# ALU.net
KiCad netlist of a schematic drawn in Altium Designer
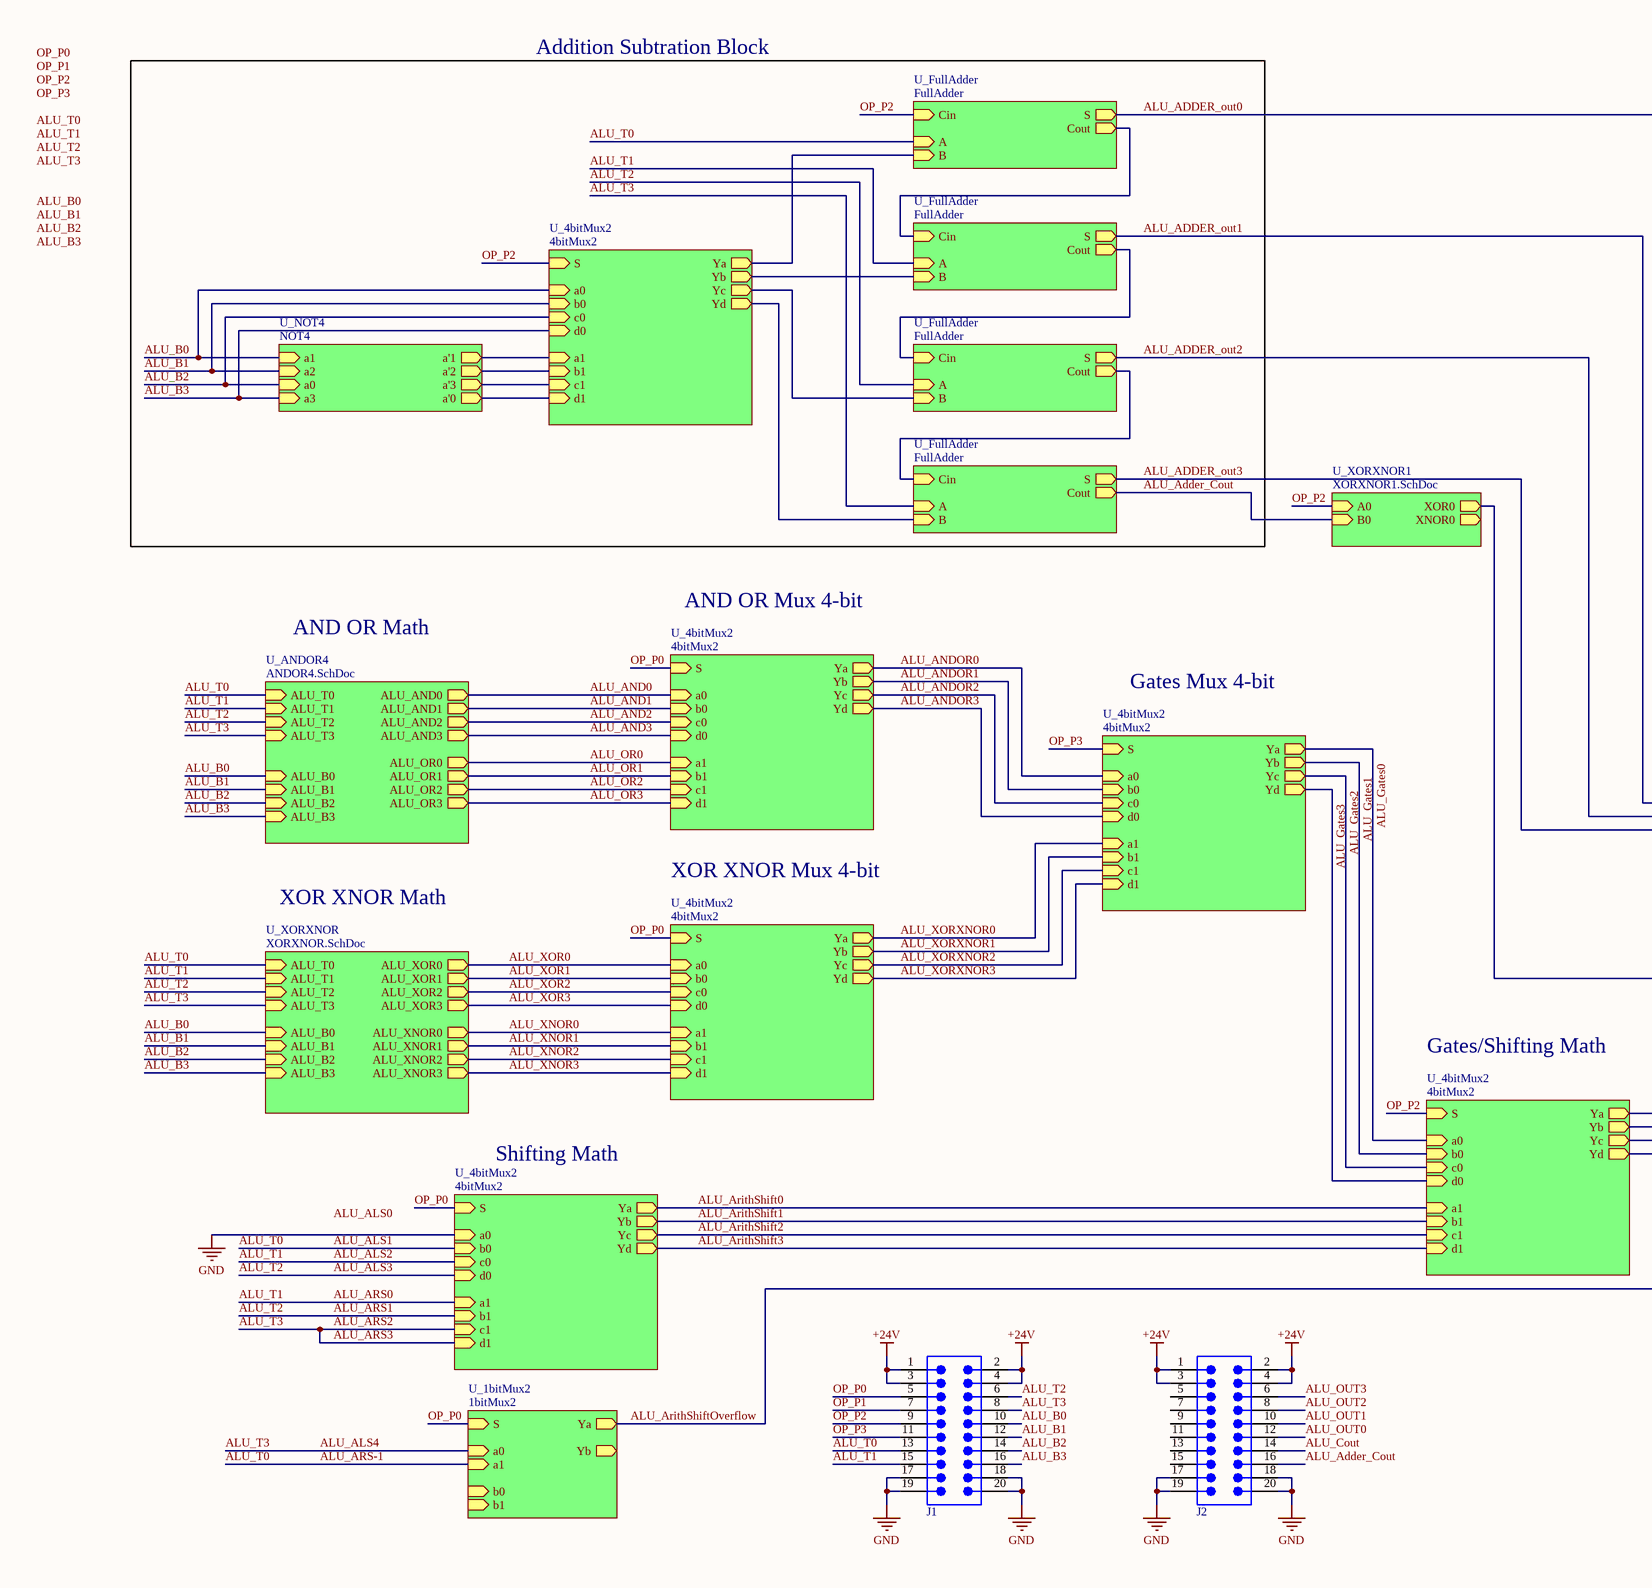
[diagram p0: ALU.SchDoc, left]
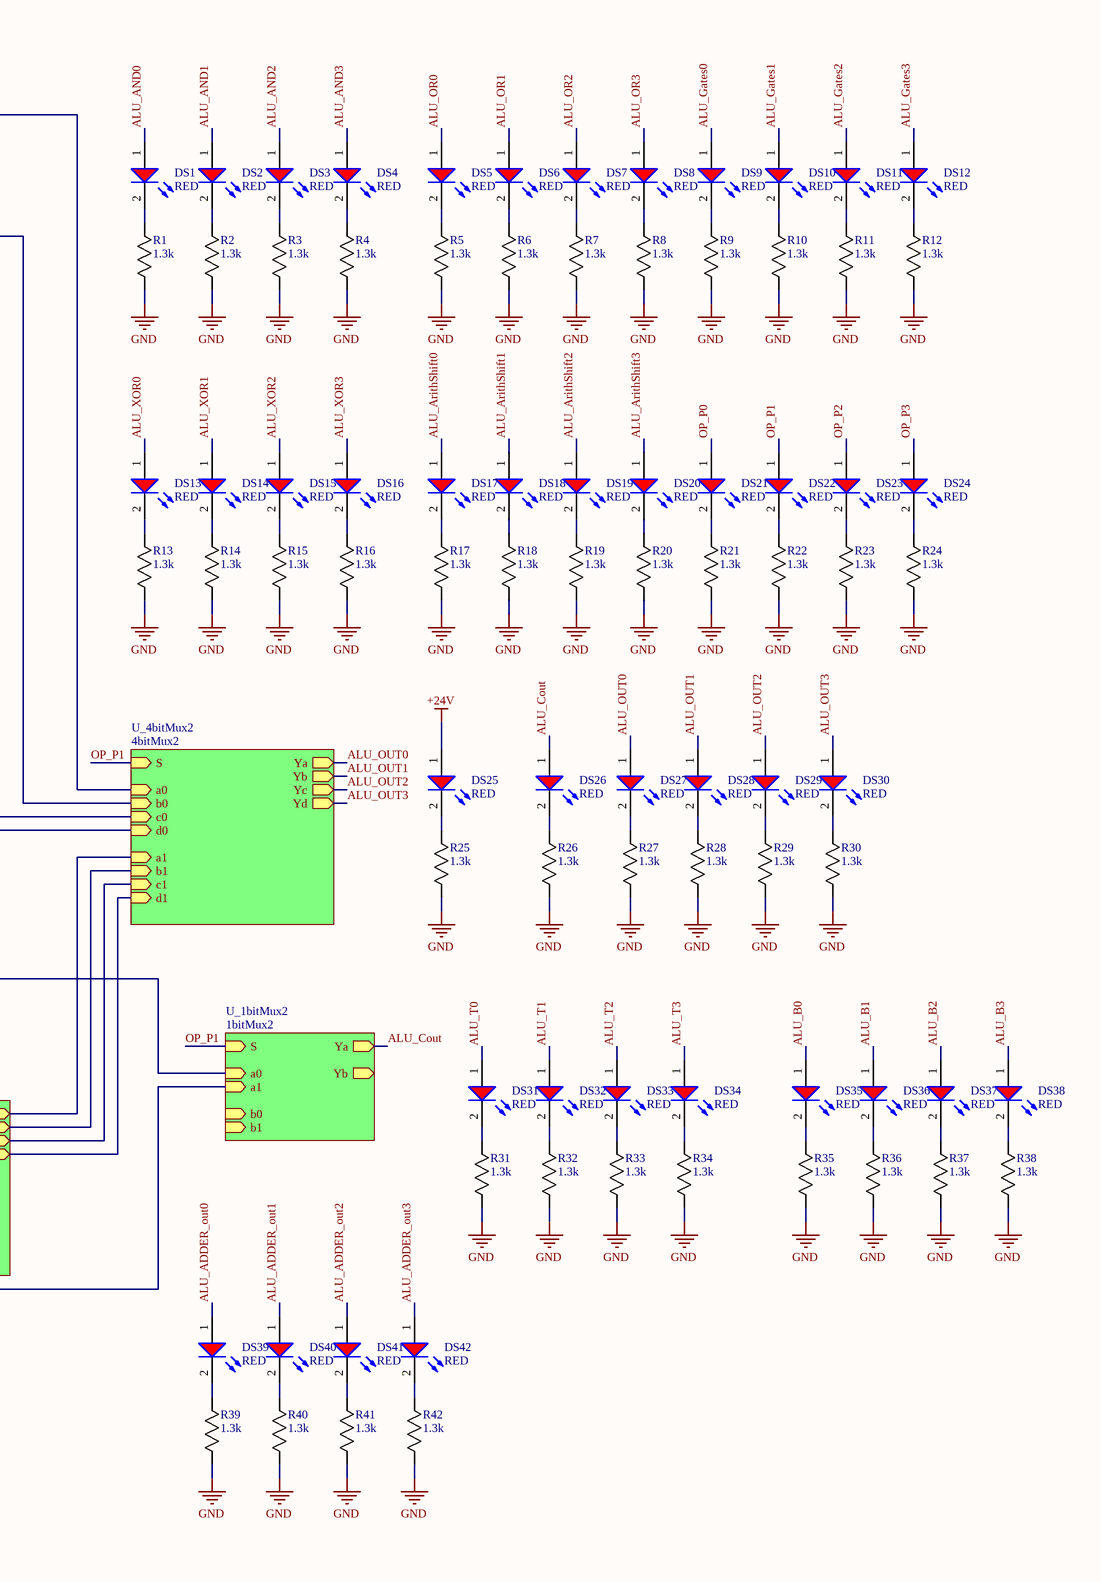
[diagram p1: ALU.SchDoc, right]

(export (version "E")
  (design (tool "Eeschema 10.0.6"))
  (components
    (comp (ref "DS1")
      (value "RED")
      (footprint "LED RED 151051RS11000")
      (description "WL-TMRC Red Color Diffused 5 mm Round Through Hole LED")
      (fields
        (field (name "MANUFACTURER") "Wurth Elektronik")
        (field (name "MANUFACTURER PART NUMBER") "151051RS11000")
      )
      (libsource (lib "Schlib1") (part "LED RED 151051RS11000"))
    )
    (comp (ref "DS2")
      (value "RED")
      (footprint "LED RED 151051RS11000")
      (description "WL-TMRC Red Color Diffused 5 mm Round Through Hole LED")
      (fields
        (field (name "MANUFACTURER") "Wurth Elektronik")
        (field (name "MANUFACTURER PART NUMBER") "151051RS11000")
      )
      (libsource (lib "Schlib1") (part "LED RED 151051RS11000"))
    )
    (comp (ref "DS3")
      (value "RED")
      (footprint "LED RED 151051RS11000")
      (description "WL-TMRC Red Color Diffused 5 mm Round Through Hole LED")
      (fields
        (field (name "MANUFACTURER") "Wurth Elektronik")
        (field (name "MANUFACTURER PART NUMBER") "151051RS11000")
      )
      (libsource (lib "Schlib1") (part "LED RED 151051RS11000"))
    )
    (comp (ref "DS4")
      (value "RED")
      (footprint "LED RED 151051RS11000")
      (description "WL-TMRC Red Color Diffused 5 mm Round Through Hole LED")
      (fields
        (field (name "MANUFACTURER") "Wurth Elektronik")
        (field (name "MANUFACTURER PART NUMBER") "151051RS11000")
      )
      (libsource (lib "Schlib1") (part "LED RED 151051RS11000"))
    )
    (comp (ref "DS5")
      (value "RED")
      (footprint "LED RED 151051RS11000")
      (description "WL-TMRC Red Color Diffused 5 mm Round Through Hole LED")
      (fields
        (field (name "MANUFACTURER") "Wurth Elektronik")
        (field (name "MANUFACTURER PART NUMBER") "151051RS11000")
      )
      (libsource (lib "Schlib1") (part "LED RED 151051RS11000"))
    )
    (comp (ref "DS6")
      (value "RED")
      (footprint "LED RED 151051RS11000")
      (description "WL-TMRC Red Color Diffused 5 mm Round Through Hole LED")
      (fields
        (field (name "MANUFACTURER") "Wurth Elektronik")
        (field (name "MANUFACTURER PART NUMBER") "151051RS11000")
      )
      (libsource (lib "Schlib1") (part "LED RED 151051RS11000"))
    )
    (comp (ref "DS7")
      (value "RED")
      (footprint "LED RED 151051RS11000")
      (description "WL-TMRC Red Color Diffused 5 mm Round Through Hole LED")
      (fields
        (field (name "MANUFACTURER") "Wurth Elektronik")
        (field (name "MANUFACTURER PART NUMBER") "151051RS11000")
      )
      (libsource (lib "Schlib1") (part "LED RED 151051RS11000"))
    )
    (comp (ref "DS8")
      (value "RED")
      (footprint "LED RED 151051RS11000")
      (description "WL-TMRC Red Color Diffused 5 mm Round Through Hole LED")
      (fields
        (field (name "MANUFACTURER") "Wurth Elektronik")
        (field (name "MANUFACTURER PART NUMBER") "151051RS11000")
      )
      (libsource (lib "Schlib1") (part "LED RED 151051RS11000"))
    )
    (comp (ref "DS9")
      (value "RED")
      (footprint "LED RED 151051RS11000")
      (description "WL-TMRC Red Color Diffused 5 mm Round Through Hole LED")
      (fields
        (field (name "MANUFACTURER") "Wurth Elektronik")
        (field (name "MANUFACTURER PART NUMBER") "151051RS11000")
      )
      (libsource (lib "Schlib1") (part "LED RED 151051RS11000"))
    )
    (comp (ref "DS10")
      (value "RED")
      (footprint "LED RED 151051RS11000")
      (description "WL-TMRC Red Color Diffused 5 mm Round Through Hole LED")
      (fields
        (field (name "MANUFACTURER") "Wurth Elektronik")
        (field (name "MANUFACTURER PART NUMBER") "151051RS11000")
      )
      (libsource (lib "Schlib1") (part "LED RED 151051RS11000"))
    )
    (comp (ref "DS11")
      (value "RED")
      (footprint "LED RED 151051RS11000")
      (description "WL-TMRC Red Color Diffused 5 mm Round Through Hole LED")
      (fields
        (field (name "MANUFACTURER") "Wurth Elektronik")
        (field (name "MANUFACTURER PART NUMBER") "151051RS11000")
      )
      (libsource (lib "Schlib1") (part "LED RED 151051RS11000"))
    )
    (comp (ref "DS12")
      (value "RED")
      (footprint "LED RED 151051RS11000")
      (description "WL-TMRC Red Color Diffused 5 mm Round Through Hole LED")
      (fields
        (field (name "MANUFACTURER") "Wurth Elektronik")
        (field (name "MANUFACTURER PART NUMBER") "151051RS11000")
      )
      (libsource (lib "Schlib1") (part "LED RED 151051RS11000"))
    )
    (comp (ref "DS13")
      (value "RED")
      (footprint "LED RED 151051RS11000")
      (description "WL-TMRC Red Color Diffused 5 mm Round Through Hole LED")
      (fields
        (field (name "MANUFACTURER") "Wurth Elektronik")
        (field (name "MANUFACTURER PART NUMBER") "151051RS11000")
      )
      (libsource (lib "Schlib1") (part "LED RED 151051RS11000"))
    )
    (comp (ref "DS14")
      (value "RED")
      (footprint "LED RED 151051RS11000")
      (description "WL-TMRC Red Color Diffused 5 mm Round Through Hole LED")
      (fields
        (field (name "MANUFACTURER") "Wurth Elektronik")
        (field (name "MANUFACTURER PART NUMBER") "151051RS11000")
      )
      (libsource (lib "Schlib1") (part "LED RED 151051RS11000"))
    )
    (comp (ref "DS15")
      (value "RED")
      (footprint "LED RED 151051RS11000")
      (description "WL-TMRC Red Color Diffused 5 mm Round Through Hole LED")
      (fields
        (field (name "MANUFACTURER") "Wurth Elektronik")
        (field (name "MANUFACTURER PART NUMBER") "151051RS11000")
      )
      (libsource (lib "Schlib1") (part "LED RED 151051RS11000"))
    )
    (comp (ref "DS16")
      (value "RED")
      (footprint "LED RED 151051RS11000")
      (description "WL-TMRC Red Color Diffused 5 mm Round Through Hole LED")
      (fields
        (field (name "MANUFACTURER") "Wurth Elektronik")
        (field (name "MANUFACTURER PART NUMBER") "151051RS11000")
      )
      (libsource (lib "Schlib1") (part "LED RED 151051RS11000"))
    )
    (comp (ref "DS17")
      (value "RED")
      (footprint "LED RED 151051RS11000")
      (description "WL-TMRC Red Color Diffused 5 mm Round Through Hole LED")
      (fields
        (field (name "MANUFACTURER") "Wurth Elektronik")
        (field (name "MANUFACTURER PART NUMBER") "151051RS11000")
      )
      (libsource (lib "Schlib1") (part "LED RED 151051RS11000"))
    )
    (comp (ref "DS18")
      (value "RED")
      (footprint "LED RED 151051RS11000")
      (description "WL-TMRC Red Color Diffused 5 mm Round Through Hole LED")
      (fields
        (field (name "MANUFACTURER") "Wurth Elektronik")
        (field (name "MANUFACTURER PART NUMBER") "151051RS11000")
      )
      (libsource (lib "Schlib1") (part "LED RED 151051RS11000"))
    )
    (comp (ref "DS19")
      (value "RED")
      (footprint "LED RED 151051RS11000")
      (description "WL-TMRC Red Color Diffused 5 mm Round Through Hole LED")
      (fields
        (field (name "MANUFACTURER") "Wurth Elektronik")
        (field (name "MANUFACTURER PART NUMBER") "151051RS11000")
      )
      (libsource (lib "Schlib1") (part "LED RED 151051RS11000"))
    )
    (comp (ref "DS20")
      (value "RED")
      (footprint "LED RED 151051RS11000")
      (description "WL-TMRC Red Color Diffused 5 mm Round Through Hole LED")
      (fields
        (field (name "MANUFACTURER") "Wurth Elektronik")
        (field (name "MANUFACTURER PART NUMBER") "151051RS11000")
      )
      (libsource (lib "Schlib1") (part "LED RED 151051RS11000"))
    )
    (comp (ref "DS21")
      (value "RED")
      (footprint "LED RED 151051RS11000")
      (description "WL-TMRC Red Color Diffused 5 mm Round Through Hole LED")
      (fields
        (field (name "MANUFACTURER") "Wurth Elektronik")
        (field (name "MANUFACTURER PART NUMBER") "151051RS11000")
      )
      (libsource (lib "Schlib1") (part "LED RED 151051RS11000"))
    )
    (comp (ref "DS22")
      (value "RED")
      (footprint "LED RED 151051RS11000")
      (description "WL-TMRC Red Color Diffused 5 mm Round Through Hole LED")
      (fields
        (field (name "MANUFACTURER") "Wurth Elektronik")
        (field (name "MANUFACTURER PART NUMBER") "151051RS11000")
      )
      (libsource (lib "Schlib1") (part "LED RED 151051RS11000"))
    )
    (comp (ref "DS23")
      (value "RED")
      (footprint "LED RED 151051RS11000")
      (description "WL-TMRC Red Color Diffused 5 mm Round Through Hole LED")
      (fields
        (field (name "MANUFACTURER") "Wurth Elektronik")
        (field (name "MANUFACTURER PART NUMBER") "151051RS11000")
      )
      (libsource (lib "Schlib1") (part "LED RED 151051RS11000"))
    )
    (comp (ref "DS24")
      (value "RED")
      (footprint "LED RED 151051RS11000")
      (description "WL-TMRC Red Color Diffused 5 mm Round Through Hole LED")
      (fields
        (field (name "MANUFACTURER") "Wurth Elektronik")
        (field (name "MANUFACTURER PART NUMBER") "151051RS11000")
      )
      (libsource (lib "Schlib1") (part "LED RED 151051RS11000"))
    )
    (comp (ref "DS25")
      (value "RED")
      (footprint "LED RED 151051RS11000")
      (description "WL-TMRC Red Color Diffused 5 mm Round Through Hole LED")
      (fields
        (field (name "MANUFACTURER") "Wurth Elektronik")
        (field (name "MANUFACTURER PART NUMBER") "151051RS11000")
      )
      (libsource (lib "Schlib1") (part "LED RED 151051RS11000"))
    )
    (comp (ref "DS26")
      (value "RED")
      (footprint "LED RED 151051RS11000")
      (description "WL-TMRC Red Color Diffused 5 mm Round Through Hole LED")
      (fields
        (field (name "MANUFACTURER") "Wurth Elektronik")
        (field (name "MANUFACTURER PART NUMBER") "151051RS11000")
      )
      (libsource (lib "Schlib1") (part "LED RED 151051RS11000"))
    )
    (comp (ref "DS27")
      (value "RED")
      (footprint "LED RED 151051RS11000")
      (description "WL-TMRC Red Color Diffused 5 mm Round Through Hole LED")
      (fields
        (field (name "MANUFACTURER") "Wurth Elektronik")
        (field (name "MANUFACTURER PART NUMBER") "151051RS11000")
      )
      (libsource (lib "Schlib1") (part "LED RED 151051RS11000"))
    )
    (comp (ref "DS28")
      (value "RED")
      (footprint "LED RED 151051RS11000")
      (description "WL-TMRC Red Color Diffused 5 mm Round Through Hole LED")
      (fields
        (field (name "MANUFACTURER") "Wurth Elektronik")
        (field (name "MANUFACTURER PART NUMBER") "151051RS11000")
      )
      (libsource (lib "Schlib1") (part "LED RED 151051RS11000"))
    )
    (comp (ref "DS29")
      (value "RED")
      (footprint "LED RED 151051RS11000")
      (description "WL-TMRC Red Color Diffused 5 mm Round Through Hole LED")
      (fields
        (field (name "MANUFACTURER") "Wurth Elektronik")
        (field (name "MANUFACTURER PART NUMBER") "151051RS11000")
      )
      (libsource (lib "Schlib1") (part "LED RED 151051RS11000"))
    )
    (comp (ref "DS30")
      (value "RED")
      (footprint "LED RED 151051RS11000")
      (description "WL-TMRC Red Color Diffused 5 mm Round Through Hole LED")
      (fields
        (field (name "MANUFACTURER") "Wurth Elektronik")
        (field (name "MANUFACTURER PART NUMBER") "151051RS11000")
      )
      (libsource (lib "Schlib1") (part "LED RED 151051RS11000"))
    )
    (comp (ref "DS31")
      (value "RED")
      (footprint "LED RED 151051RS11000")
      (description "WL-TMRC Red Color Diffused 5 mm Round Through Hole LED")
      (fields
        (field (name "MANUFACTURER") "Wurth Elektronik")
        (field (name "MANUFACTURER PART NUMBER") "151051RS11000")
      )
      (libsource (lib "Schlib1") (part "LED RED 151051RS11000"))
    )
    (comp (ref "DS32")
      (value "RED")
      (footprint "LED RED 151051RS11000")
      (description "WL-TMRC Red Color Diffused 5 mm Round Through Hole LED")
      (fields
        (field (name "MANUFACTURER") "Wurth Elektronik")
        (field (name "MANUFACTURER PART NUMBER") "151051RS11000")
      )
      (libsource (lib "Schlib1") (part "LED RED 151051RS11000"))
    )
    (comp (ref "DS33")
      (value "RED")
      (footprint "LED RED 151051RS11000")
      (description "WL-TMRC Red Color Diffused 5 mm Round Through Hole LED")
      (fields
        (field (name "MANUFACTURER") "Wurth Elektronik")
        (field (name "MANUFACTURER PART NUMBER") "151051RS11000")
      )
      (libsource (lib "Schlib1") (part "LED RED 151051RS11000"))
    )
    (comp (ref "DS34")
      (value "RED")
      (footprint "LED RED 151051RS11000")
      (description "WL-TMRC Red Color Diffused 5 mm Round Through Hole LED")
      (fields
        (field (name "MANUFACTURER") "Wurth Elektronik")
        (field (name "MANUFACTURER PART NUMBER") "151051RS11000")
      )
      (libsource (lib "Schlib1") (part "LED RED 151051RS11000"))
    )
    (comp (ref "DS35")
      (value "RED")
      (footprint "LED RED 151051RS11000")
      (description "WL-TMRC Red Color Diffused 5 mm Round Through Hole LED")
      (fields
        (field (name "MANUFACTURER") "Wurth Elektronik")
        (field (name "MANUFACTURER PART NUMBER") "151051RS11000")
      )
      (libsource (lib "Schlib1") (part "LED RED 151051RS11000"))
    )
    (comp (ref "DS36")
      (value "RED")
      (footprint "LED RED 151051RS11000")
      (description "WL-TMRC Red Color Diffused 5 mm Round Through Hole LED")
      (fields
        (field (name "MANUFACTURER") "Wurth Elektronik")
        (field (name "MANUFACTURER PART NUMBER") "151051RS11000")
      )
      (libsource (lib "Schlib1") (part "LED RED 151051RS11000"))
    )
    (comp (ref "DS37")
      (value "RED")
      (footprint "LED RED 151051RS11000")
      (description "WL-TMRC Red Color Diffused 5 mm Round Through Hole LED")
      (fields
        (field (name "MANUFACTURER") "Wurth Elektronik")
        (field (name "MANUFACTURER PART NUMBER") "151051RS11000")
      )
      (libsource (lib "Schlib1") (part "LED RED 151051RS11000"))
    )
    (comp (ref "DS38")
      (value "RED")
      (footprint "LED RED 151051RS11000")
      (description "WL-TMRC Red Color Diffused 5 mm Round Through Hole LED")
      (fields
        (field (name "MANUFACTURER") "Wurth Elektronik")
        (field (name "MANUFACTURER PART NUMBER") "151051RS11000")
      )
      (libsource (lib "Schlib1") (part "LED RED 151051RS11000"))
    )
    (comp (ref "DS39")
      (value "RED")
      (footprint "LED RED 151051RS11000")
      (description "WL-TMRC Red Color Diffused 5 mm Round Through Hole LED")
      (fields
        (field (name "MANUFACTURER") "Wurth Elektronik")
        (field (name "MANUFACTURER PART NUMBER") "151051RS11000")
      )
      (libsource (lib "Schlib1") (part "LED RED 151051RS11000"))
    )
    (comp (ref "DS40")
      (value "RED")
      (footprint "LED RED 151051RS11000")
      (description "WL-TMRC Red Color Diffused 5 mm Round Through Hole LED")
      (fields
        (field (name "MANUFACTURER") "Wurth Elektronik")
        (field (name "MANUFACTURER PART NUMBER") "151051RS11000")
      )
      (libsource (lib "Schlib1") (part "LED RED 151051RS11000"))
    )
    (comp (ref "DS41")
      (value "RED")
      (footprint "LED RED 151051RS11000")
      (description "WL-TMRC Red Color Diffused 5 mm Round Through Hole LED")
      (fields
        (field (name "MANUFACTURER") "Wurth Elektronik")
        (field (name "MANUFACTURER PART NUMBER") "151051RS11000")
      )
      (libsource (lib "Schlib1") (part "LED RED 151051RS11000"))
    )
    (comp (ref "DS42")
      (value "RED")
      (footprint "LED RED 151051RS11000")
      (description "WL-TMRC Red Color Diffused 5 mm Round Through Hole LED")
      (fields
        (field (name "MANUFACTURER") "Wurth Elektronik")
        (field (name "MANUFACTURER PART NUMBER") "151051RS11000")
      )
      (libsource (lib "Schlib1") (part "LED RED 151051RS11000"))
    )
    (comp (ref "J1")
      (value "Con 61202021621")
      (footprint "Con 61202021621")
      (description "WR-BHD Straight Male, Box Header, Through Hole, 2 Rows, 20 Contacts, 2.54mm Pitch")
      (fields
        (field (name "MANUFACTURER") "Wurth Elektronik")
        (field (name "MANUFACTURER PART NUMBER") "61202021621")
      )
      (libsource (lib "Schlib1") (part "Con 61202021621"))
    )
    (comp (ref "J2")
      (value "Con 61202021621")
      (footprint "Con 61202021621")
      (description "WR-BHD Straight Male, Box Header, Through Hole, 2 Rows, 20 Contacts, 2.54mm Pitch")
      (fields
        (field (name "MANUFACTURER") "Wurth Elektronik")
        (field (name "MANUFACTURER PART NUMBER") "61202021621")
      )
      (libsource (lib "Schlib1") (part "Con 61202021621"))
    )
    (comp (ref "R1")
      (value "1.3k")
      (footprint "RES 2512")
      (description "Res Thick Film 2512 1.3K Ohm 1% 1W ±100ppm/C Pad SMD Automotive T/R RMCF2512FT1K30")
      (fields
        (field (name "MANUFACTURER") "Stackpole Electronics")
        (field (name "MANUFACTURER PART NUMBER") "RMCF2512FT1K30")
      )
      (libsource (lib "Schlib1") (part "RES 1.3k 2512 1W"))
    )
    (comp (ref "R2")
      (value "1.3k")
      (footprint "RES 2512")
      (description "Res Thick Film 2512 1.3K Ohm 1% 1W ±100ppm/C Pad SMD Automotive T/R RMCF2512FT1K30")
      (fields
        (field (name "MANUFACTURER") "Stackpole Electronics")
        (field (name "MANUFACTURER PART NUMBER") "RMCF2512FT1K30")
      )
      (libsource (lib "Schlib1") (part "RES 1.3k 2512 1W"))
    )
    (comp (ref "R3")
      (value "1.3k")
      (footprint "RES 2512")
      (description "Res Thick Film 2512 1.3K Ohm 1% 1W ±100ppm/C Pad SMD Automotive T/R RMCF2512FT1K30")
      (fields
        (field (name "MANUFACTURER") "Stackpole Electronics")
        (field (name "MANUFACTURER PART NUMBER") "RMCF2512FT1K30")
      )
      (libsource (lib "Schlib1") (part "RES 1.3k 2512 1W"))
    )
    (comp (ref "R4")
      (value "1.3k")
      (footprint "RES 2512")
      (description "Res Thick Film 2512 1.3K Ohm 1% 1W ±100ppm/C Pad SMD Automotive T/R RMCF2512FT1K30")
      (fields
        (field (name "MANUFACTURER") "Stackpole Electronics")
        (field (name "MANUFACTURER PART NUMBER") "RMCF2512FT1K30")
      )
      (libsource (lib "Schlib1") (part "RES 1.3k 2512 1W"))
    )
    (comp (ref "R5")
      (value "1.3k")
      (footprint "RES 2512")
      (description "Res Thick Film 2512 1.3K Ohm 1% 1W ±100ppm/C Pad SMD Automotive T/R RMCF2512FT1K30")
      (fields
        (field (name "MANUFACTURER") "Stackpole Electronics")
        (field (name "MANUFACTURER PART NUMBER") "RMCF2512FT1K30")
      )
      (libsource (lib "Schlib1") (part "RES 1.3k 2512 1W"))
    )
    (comp (ref "R6")
      (value "1.3k")
      (footprint "RES 2512")
      (description "Res Thick Film 2512 1.3K Ohm 1% 1W ±100ppm/C Pad SMD Automotive T/R RMCF2512FT1K30")
      (fields
        (field (name "MANUFACTURER") "Stackpole Electronics")
        (field (name "MANUFACTURER PART NUMBER") "RMCF2512FT1K30")
      )
      (libsource (lib "Schlib1") (part "RES 1.3k 2512 1W"))
    )
    (comp (ref "R7")
      (value "1.3k")
      (footprint "RES 2512")
      (description "Res Thick Film 2512 1.3K Ohm 1% 1W ±100ppm/C Pad SMD Automotive T/R RMCF2512FT1K30")
      (fields
        (field (name "MANUFACTURER") "Stackpole Electronics")
        (field (name "MANUFACTURER PART NUMBER") "RMCF2512FT1K30")
      )
      (libsource (lib "Schlib1") (part "RES 1.3k 2512 1W"))
    )
    (comp (ref "R8")
      (value "1.3k")
      (footprint "RES 2512")
      (description "Res Thick Film 2512 1.3K Ohm 1% 1W ±100ppm/C Pad SMD Automotive T/R RMCF2512FT1K30")
      (fields
        (field (name "MANUFACTURER") "Stackpole Electronics")
        (field (name "MANUFACTURER PART NUMBER") "RMCF2512FT1K30")
      )
      (libsource (lib "Schlib1") (part "RES 1.3k 2512 1W"))
    )
    (comp (ref "R9")
      (value "1.3k")
      (footprint "RES 2512")
      (description "Res Thick Film 2512 1.3K Ohm 1% 1W ±100ppm/C Pad SMD Automotive T/R RMCF2512FT1K30")
      (fields
        (field (name "MANUFACTURER") "Stackpole Electronics")
        (field (name "MANUFACTURER PART NUMBER") "RMCF2512FT1K30")
      )
      (libsource (lib "Schlib1") (part "RES 1.3k 2512 1W"))
    )
    (comp (ref "R10")
      (value "1.3k")
      (footprint "RES 2512")
      (description "Res Thick Film 2512 1.3K Ohm 1% 1W ±100ppm/C Pad SMD Automotive T/R RMCF2512FT1K30")
      (fields
        (field (name "MANUFACTURER") "Stackpole Electronics")
        (field (name "MANUFACTURER PART NUMBER") "RMCF2512FT1K30")
      )
      (libsource (lib "Schlib1") (part "RES 1.3k 2512 1W"))
    )
    (comp (ref "R11")
      (value "1.3k")
      (footprint "RES 2512")
      (description "Res Thick Film 2512 1.3K Ohm 1% 1W ±100ppm/C Pad SMD Automotive T/R RMCF2512FT1K30")
      (fields
        (field (name "MANUFACTURER") "Stackpole Electronics")
        (field (name "MANUFACTURER PART NUMBER") "RMCF2512FT1K30")
      )
      (libsource (lib "Schlib1") (part "RES 1.3k 2512 1W"))
    )
    (comp (ref "R12")
      (value "1.3k")
      (footprint "RES 2512")
      (description "Res Thick Film 2512 1.3K Ohm 1% 1W ±100ppm/C Pad SMD Automotive T/R RMCF2512FT1K30")
      (fields
        (field (name "MANUFACTURER") "Stackpole Electronics")
        (field (name "MANUFACTURER PART NUMBER") "RMCF2512FT1K30")
      )
      (libsource (lib "Schlib1") (part "RES 1.3k 2512 1W"))
    )
    (comp (ref "R13")
      (value "1.3k")
      (footprint "RES 2512")
      (description "Res Thick Film 2512 1.3K Ohm 1% 1W ±100ppm/C Pad SMD Automotive T/R RMCF2512FT1K30")
      (fields
        (field (name "MANUFACTURER") "Stackpole Electronics")
        (field (name "MANUFACTURER PART NUMBER") "RMCF2512FT1K30")
      )
      (libsource (lib "Schlib1") (part "RES 1.3k 2512 1W"))
    )
    (comp (ref "R14")
      (value "1.3k")
      (footprint "RES 2512")
      (description "Res Thick Film 2512 1.3K Ohm 1% 1W ±100ppm/C Pad SMD Automotive T/R RMCF2512FT1K30")
      (fields
        (field (name "MANUFACTURER") "Stackpole Electronics")
        (field (name "MANUFACTURER PART NUMBER") "RMCF2512FT1K30")
      )
      (libsource (lib "Schlib1") (part "RES 1.3k 2512 1W"))
    )
    (comp (ref "R15")
      (value "1.3k")
      (footprint "RES 2512")
      (description "Res Thick Film 2512 1.3K Ohm 1% 1W ±100ppm/C Pad SMD Automotive T/R RMCF2512FT1K30")
      (fields
        (field (name "MANUFACTURER") "Stackpole Electronics")
        (field (name "MANUFACTURER PART NUMBER") "RMCF2512FT1K30")
      )
      (libsource (lib "Schlib1") (part "RES 1.3k 2512 1W"))
    )
    (comp (ref "R16")
      (value "1.3k")
      (footprint "RES 2512")
      (description "Res Thick Film 2512 1.3K Ohm 1% 1W ±100ppm/C Pad SMD Automotive T/R RMCF2512FT1K30")
      (fields
        (field (name "MANUFACTURER") "Stackpole Electronics")
        (field (name "MANUFACTURER PART NUMBER") "RMCF2512FT1K30")
      )
      (libsource (lib "Schlib1") (part "RES 1.3k 2512 1W"))
    )
    (comp (ref "R17")
      (value "1.3k")
      (footprint "RES 2512")
      (description "Res Thick Film 2512 1.3K Ohm 1% 1W ±100ppm/C Pad SMD Automotive T/R RMCF2512FT1K30")
      (fields
        (field (name "MANUFACTURER") "Stackpole Electronics")
        (field (name "MANUFACTURER PART NUMBER") "RMCF2512FT1K30")
      )
      (libsource (lib "Schlib1") (part "RES 1.3k 2512 1W"))
    )
    (comp (ref "R18")
      (value "1.3k")
      (footprint "RES 2512")
      (description "Res Thick Film 2512 1.3K Ohm 1% 1W ±100ppm/C Pad SMD Automotive T/R RMCF2512FT1K30")
      (fields
        (field (name "MANUFACTURER") "Stackpole Electronics")
        (field (name "MANUFACTURER PART NUMBER") "RMCF2512FT1K30")
      )
      (libsource (lib "Schlib1") (part "RES 1.3k 2512 1W"))
    )
    (comp (ref "R19")
      (value "1.3k")
      (footprint "RES 2512")
      (description "Res Thick Film 2512 1.3K Ohm 1% 1W ±100ppm/C Pad SMD Automotive T/R RMCF2512FT1K30")
      (fields
        (field (name "MANUFACTURER") "Stackpole Electronics")
        (field (name "MANUFACTURER PART NUMBER") "RMCF2512FT1K30")
      )
      (libsource (lib "Schlib1") (part "RES 1.3k 2512 1W"))
    )
    (comp (ref "R20")
      (value "1.3k")
      (footprint "RES 2512")
      (description "Res Thick Film 2512 1.3K Ohm 1% 1W ±100ppm/C Pad SMD Automotive T/R RMCF2512FT1K30")
      (fields
        (field (name "MANUFACTURER") "Stackpole Electronics")
        (field (name "MANUFACTURER PART NUMBER") "RMCF2512FT1K30")
      )
      (libsource (lib "Schlib1") (part "RES 1.3k 2512 1W"))
    )
    (comp (ref "R21")
      (value "1.3k")
      (footprint "RES 2512")
      (description "Res Thick Film 2512 1.3K Ohm 1% 1W ±100ppm/C Pad SMD Automotive T/R RMCF2512FT1K30")
      (fields
        (field (name "MANUFACTURER") "Stackpole Electronics")
        (field (name "MANUFACTURER PART NUMBER") "RMCF2512FT1K30")
      )
      (libsource (lib "Schlib1") (part "RES 1.3k 2512 1W"))
    )
    (comp (ref "R22")
      (value "1.3k")
      (footprint "RES 2512")
      (description "Res Thick Film 2512 1.3K Ohm 1% 1W ±100ppm/C Pad SMD Automotive T/R RMCF2512FT1K30")
      (fields
        (field (name "MANUFACTURER") "Stackpole Electronics")
        (field (name "MANUFACTURER PART NUMBER") "RMCF2512FT1K30")
      )
      (libsource (lib "Schlib1") (part "RES 1.3k 2512 1W"))
    )
    (comp (ref "R23")
      (value "1.3k")
      (footprint "RES 2512")
      (description "Res Thick Film 2512 1.3K Ohm 1% 1W ±100ppm/C Pad SMD Automotive T/R RMCF2512FT1K30")
      (fields
        (field (name "MANUFACTURER") "Stackpole Electronics")
        (field (name "MANUFACTURER PART NUMBER") "RMCF2512FT1K30")
      )
      (libsource (lib "Schlib1") (part "RES 1.3k 2512 1W"))
    )
    (comp (ref "R24")
      (value "1.3k")
      (footprint "RES 2512")
      (description "Res Thick Film 2512 1.3K Ohm 1% 1W ±100ppm/C Pad SMD Automotive T/R RMCF2512FT1K30")
      (fields
        (field (name "MANUFACTURER") "Stackpole Electronics")
        (field (name "MANUFACTURER PART NUMBER") "RMCF2512FT1K30")
      )
      (libsource (lib "Schlib1") (part "RES 1.3k 2512 1W"))
    )
    (comp (ref "R25")
      (value "1.3k")
      (footprint "RES 2512")
      (description "Res Thick Film 2512 1.3K Ohm 1% 1W ±100ppm/C Pad SMD Automotive T/R RMCF2512FT1K30")
      (fields
        (field (name "MANUFACTURER") "Stackpole Electronics")
        (field (name "MANUFACTURER PART NUMBER") "RMCF2512FT1K30")
      )
      (libsource (lib "Schlib1") (part "RES 1.3k 2512 1W"))
    )
    (comp (ref "R26")
      (value "1.3k")
      (footprint "RES 2512")
      (description "Res Thick Film 2512 1.3K Ohm 1% 1W ±100ppm/C Pad SMD Automotive T/R RMCF2512FT1K30")
      (fields
        (field (name "MANUFACTURER") "Stackpole Electronics")
        (field (name "MANUFACTURER PART NUMBER") "RMCF2512FT1K30")
      )
      (libsource (lib "Schlib1") (part "RES 1.3k 2512 1W"))
    )
    (comp (ref "R27")
      (value "1.3k")
      (footprint "RES 2512")
      (description "Res Thick Film 2512 1.3K Ohm 1% 1W ±100ppm/C Pad SMD Automotive T/R RMCF2512FT1K30")
      (fields
        (field (name "MANUFACTURER") "Stackpole Electronics")
        (field (name "MANUFACTURER PART NUMBER") "RMCF2512FT1K30")
      )
      (libsource (lib "Schlib1") (part "RES 1.3k 2512 1W"))
    )
    (comp (ref "R28")
      (value "1.3k")
      (footprint "RES 2512")
      (description "Res Thick Film 2512 1.3K Ohm 1% 1W ±100ppm/C Pad SMD Automotive T/R RMCF2512FT1K30")
      (fields
        (field (name "MANUFACTURER") "Stackpole Electronics")
        (field (name "MANUFACTURER PART NUMBER") "RMCF2512FT1K30")
      )
      (libsource (lib "Schlib1") (part "RES 1.3k 2512 1W"))
    )
    (comp (ref "R29")
      (value "1.3k")
      (footprint "RES 2512")
      (description "Res Thick Film 2512 1.3K Ohm 1% 1W ±100ppm/C Pad SMD Automotive T/R RMCF2512FT1K30")
      (fields
        (field (name "MANUFACTURER") "Stackpole Electronics")
        (field (name "MANUFACTURER PART NUMBER") "RMCF2512FT1K30")
      )
      (libsource (lib "Schlib1") (part "RES 1.3k 2512 1W"))
    )
    (comp (ref "R30")
      (value "1.3k")
      (footprint "RES 2512")
      (description "Res Thick Film 2512 1.3K Ohm 1% 1W ±100ppm/C Pad SMD Automotive T/R RMCF2512FT1K30")
      (fields
        (field (name "MANUFACTURER") "Stackpole Electronics")
        (field (name "MANUFACTURER PART NUMBER") "RMCF2512FT1K30")
      )
      (libsource (lib "Schlib1") (part "RES 1.3k 2512 1W"))
    )
    (comp (ref "R31")
      (value "1.3k")
      (footprint "RES 2512")
      (description "Res Thick Film 2512 1.3K Ohm 1% 1W ±100ppm/C Pad SMD Automotive T/R RMCF2512FT1K30")
      (fields
        (field (name "MANUFACTURER") "Stackpole Electronics")
        (field (name "MANUFACTURER PART NUMBER") "RMCF2512FT1K30")
      )
      (libsource (lib "Schlib1") (part "RES 1.3k 2512 1W"))
    )
    (comp (ref "R32")
      (value "1.3k")
      (footprint "RES 2512")
      (description "Res Thick Film 2512 1.3K Ohm 1% 1W ±100ppm/C Pad SMD Automotive T/R RMCF2512FT1K30")
      (fields
        (field (name "MANUFACTURER") "Stackpole Electronics")
        (field (name "MANUFACTURER PART NUMBER") "RMCF2512FT1K30")
      )
      (libsource (lib "Schlib1") (part "RES 1.3k 2512 1W"))
    )
    (comp (ref "R33")
      (value "1.3k")
      (footprint "RES 2512")
      (description "Res Thick Film 2512 1.3K Ohm 1% 1W ±100ppm/C Pad SMD Automotive T/R RMCF2512FT1K30")
      (fields
        (field (name "MANUFACTURER") "Stackpole Electronics")
        (field (name "MANUFACTURER PART NUMBER") "RMCF2512FT1K30")
      )
      (libsource (lib "Schlib1") (part "RES 1.3k 2512 1W"))
    )
    (comp (ref "R34")
      (value "1.3k")
      (footprint "RES 2512")
      (description "Res Thick Film 2512 1.3K Ohm 1% 1W ±100ppm/C Pad SMD Automotive T/R RMCF2512FT1K30")
      (fields
        (field (name "MANUFACTURER") "Stackpole Electronics")
        (field (name "MANUFACTURER PART NUMBER") "RMCF2512FT1K30")
      )
      (libsource (lib "Schlib1") (part "RES 1.3k 2512 1W"))
    )
    (comp (ref "R35")
      (value "1.3k")
      (footprint "RES 2512")
      (description "Res Thick Film 2512 1.3K Ohm 1% 1W ±100ppm/C Pad SMD Automotive T/R RMCF2512FT1K30")
      (fields
        (field (name "MANUFACTURER") "Stackpole Electronics")
        (field (name "MANUFACTURER PART NUMBER") "RMCF2512FT1K30")
      )
      (libsource (lib "Schlib1") (part "RES 1.3k 2512 1W"))
    )
    (comp (ref "R36")
      (value "1.3k")
      (footprint "RES 2512")
      (description "Res Thick Film 2512 1.3K Ohm 1% 1W ±100ppm/C Pad SMD Automotive T/R RMCF2512FT1K30")
      (fields
        (field (name "MANUFACTURER") "Stackpole Electronics")
        (field (name "MANUFACTURER PART NUMBER") "RMCF2512FT1K30")
      )
      (libsource (lib "Schlib1") (part "RES 1.3k 2512 1W"))
    )
    (comp (ref "R37")
      (value "1.3k")
      (footprint "RES 2512")
      (description "Res Thick Film 2512 1.3K Ohm 1% 1W ±100ppm/C Pad SMD Automotive T/R RMCF2512FT1K30")
      (fields
        (field (name "MANUFACTURER") "Stackpole Electronics")
        (field (name "MANUFACTURER PART NUMBER") "RMCF2512FT1K30")
      )
      (libsource (lib "Schlib1") (part "RES 1.3k 2512 1W"))
    )
    (comp (ref "R38")
      (value "1.3k")
      (footprint "RES 2512")
      (description "Res Thick Film 2512 1.3K Ohm 1% 1W ±100ppm/C Pad SMD Automotive T/R RMCF2512FT1K30")
      (fields
        (field (name "MANUFACTURER") "Stackpole Electronics")
        (field (name "MANUFACTURER PART NUMBER") "RMCF2512FT1K30")
      )
      (libsource (lib "Schlib1") (part "RES 1.3k 2512 1W"))
    )
    (comp (ref "R39")
      (value "1.3k")
      (footprint "RES 2512")
      (description "Res Thick Film 2512 1.3K Ohm 1% 1W ±100ppm/C Pad SMD Automotive T/R RMCF2512FT1K30")
      (fields
        (field (name "MANUFACTURER") "Stackpole Electronics")
        (field (name "MANUFACTURER PART NUMBER") "RMCF2512FT1K30")
      )
      (libsource (lib "Schlib1") (part "RES 1.3k 2512 1W"))
    )
    (comp (ref "R40")
      (value "1.3k")
      (footprint "RES 2512")
      (description "Res Thick Film 2512 1.3K Ohm 1% 1W ±100ppm/C Pad SMD Automotive T/R RMCF2512FT1K30")
      (fields
        (field (name "MANUFACTURER") "Stackpole Electronics")
        (field (name "MANUFACTURER PART NUMBER") "RMCF2512FT1K30")
      )
      (libsource (lib "Schlib1") (part "RES 1.3k 2512 1W"))
    )
    (comp (ref "R41")
      (value "1.3k")
      (footprint "RES 2512")
      (description "Res Thick Film 2512 1.3K Ohm 1% 1W ±100ppm/C Pad SMD Automotive T/R RMCF2512FT1K30")
      (fields
        (field (name "MANUFACTURER") "Stackpole Electronics")
        (field (name "MANUFACTURER PART NUMBER") "RMCF2512FT1K30")
      )
      (libsource (lib "Schlib1") (part "RES 1.3k 2512 1W"))
    )
    (comp (ref "R42")
      (value "1.3k")
      (footprint "RES 2512")
      (description "Res Thick Film 2512 1.3K Ohm 1% 1W ±100ppm/C Pad SMD Automotive T/R RMCF2512FT1K30")
      (fields
        (field (name "MANUFACTURER") "Stackpole Electronics")
        (field (name "MANUFACTURER PART NUMBER") "RMCF2512FT1K30")
      )
      (libsource (lib "Schlib1") (part "RES 1.3k 2512 1W"))
    )
  )
  (nets
    (net (code "1") (name "+24V") (class "Default")
      (node (ref "DS25") (pin "1") (pinfunction "A_1") (pintype "passive"))
      (node (ref "J1") (pin "1") (pinfunction "1_1") (pintype "passive"))
      (node (ref "J1") (pin "2") (pinfunction "2_2") (pintype "passive"))
      (node (ref "J1") (pin "3") (pinfunction "3_3") (pintype "passive"))
      (node (ref "J1") (pin "4") (pinfunction "4_4") (pintype "passive"))
      (node (ref "J2") (pin "1") (pinfunction "1_1") (pintype "passive"))
      (node (ref "J2") (pin "2") (pinfunction "2_2") (pintype "passive"))
      (node (ref "J2") (pin "3") (pinfunction "3_3") (pintype "passive"))
      (node (ref "J2") (pin "4") (pinfunction "4_4") (pintype "passive"))
    )
    (net (code "2") (name "/ALU_ADDER_out0") (class "Default")
      (node (ref "DS39") (pin "1") (pinfunction "A_1") (pintype "passive"))
    )
    (net (code "3") (name "/ALU_ADDER_out1") (class "Default")
      (node (ref "DS40") (pin "1") (pinfunction "A_1") (pintype "passive"))
    )
    (net (code "4") (name "/ALU_ADDER_out2") (class "Default")
      (node (ref "DS41") (pin "1") (pinfunction "A_1") (pintype "passive"))
    )
    (net (code "5") (name "/ALU_ADDER_out3") (class "Default")
      (node (ref "DS42") (pin "1") (pinfunction "A_1") (pintype "passive"))
    )
    (net (code "7") (name "/ALU_ALS1") (class "Default")
      (node (ref "DS31") (pin "1") (pinfunction "A_1") (pintype "passive"))
      (node (ref "J1") (pin "13") (pinfunction "13_13") (pintype "passive"))
    )
    (net (code "8") (name "/ALU_ALS2") (class "Default")
      (node (ref "DS32") (pin "1") (pinfunction "A_1") (pintype "passive"))
      (node (ref "J1") (pin "15") (pinfunction "15_15") (pintype "passive"))
    )
    (net (code "9") (name "/ALU_ALS3") (class "Default")
      (node (ref "DS33") (pin "1") (pinfunction "A_1") (pintype "passive"))
      (node (ref "J1") (pin "6") (pinfunction "6_6") (pintype "passive"))
    )
    (net (code "10") (name "/ALU_ALS4") (class "Default")
      (node (ref "DS34") (pin "1") (pinfunction "A_1") (pintype "passive"))
      (node (ref "J1") (pin "8") (pinfunction "8_8") (pintype "passive"))
    )
    (net (code "11") (name "/ALU_AND0") (class "Default")
      (node (ref "DS1") (pin "1") (pinfunction "A_1") (pintype "passive"))
    )
    (net (code "12") (name "/ALU_AND1") (class "Default")
      (node (ref "DS2") (pin "1") (pinfunction "A_1") (pintype "passive"))
    )
    (net (code "13") (name "/ALU_AND2") (class "Default")
      (node (ref "DS3") (pin "1") (pinfunction "A_1") (pintype "passive"))
    )
    (net (code "14") (name "/ALU_AND3") (class "Default")
      (node (ref "DS4") (pin "1") (pinfunction "A_1") (pintype "passive"))
    )
    (net (code "19") (name "/ALU_Adder_Cout") (class "Default")
      (node (ref "J2") (pin "16") (pinfunction "16_16") (pintype "passive"))
    )
    (net (code "20") (name "/ALU_ArithShift0") (class "Default")
      (node (ref "DS17") (pin "1") (pinfunction "A_1") (pintype "passive"))
    )
    (net (code "21") (name "/ALU_ArithShift1") (class "Default")
      (node (ref "DS18") (pin "1") (pinfunction "A_1") (pintype "passive"))
    )
    (net (code "22") (name "/ALU_ArithShift2") (class "Default")
      (node (ref "DS19") (pin "1") (pinfunction "A_1") (pintype "passive"))
    )
    (net (code "23") (name "/ALU_ArithShift3") (class "Default")
      (node (ref "DS20") (pin "1") (pinfunction "A_1") (pintype "passive"))
    )
    (net (code "25") (name "/ALU_B0") (class "Default")
      (node (ref "DS35") (pin "1") (pinfunction "A_1") (pintype "passive"))
      (node (ref "J1") (pin "10") (pinfunction "10_10") (pintype "passive"))
    )
    (net (code "26") (name "/ALU_B1") (class "Default")
      (node (ref "DS36") (pin "1") (pinfunction "A_1") (pintype "passive"))
      (node (ref "J1") (pin "12") (pinfunction "12_12") (pintype "passive"))
    )
    (net (code "27") (name "/ALU_B2") (class "Default")
      (node (ref "DS37") (pin "1") (pinfunction "A_1") (pintype "passive"))
      (node (ref "J1") (pin "14") (pinfunction "14_14") (pintype "passive"))
    )
    (net (code "28") (name "/ALU_B3") (class "Default")
      (node (ref "DS38") (pin "1") (pinfunction "A_1") (pintype "passive"))
      (node (ref "J1") (pin "16") (pinfunction "16_16") (pintype "passive"))
    )
    (net (code "29") (name "/ALU_Cout") (class "Default")
      (node (ref "DS26") (pin "1") (pinfunction "A_1") (pintype "passive"))
      (node (ref "J2") (pin "14") (pinfunction "14_14") (pintype "passive"))
    )
    (net (code "30") (name "/ALU_Gates0") (class "Default")
      (node (ref "DS9") (pin "1") (pinfunction "A_1") (pintype "passive"))
    )
    (net (code "31") (name "/ALU_Gates1") (class "Default")
      (node (ref "DS10") (pin "1") (pinfunction "A_1") (pintype "passive"))
    )
    (net (code "32") (name "/ALU_Gates2") (class "Default")
      (node (ref "DS11") (pin "1") (pinfunction "A_1") (pintype "passive"))
    )
    (net (code "33") (name "/ALU_Gates3") (class "Default")
      (node (ref "DS12") (pin "1") (pinfunction "A_1") (pintype "passive"))
    )
    (net (code "34") (name "/ALU_OR0") (class "Default")
      (node (ref "DS5") (pin "1") (pinfunction "A_1") (pintype "passive"))
    )
    (net (code "35") (name "/ALU_OR1") (class "Default")
      (node (ref "DS6") (pin "1") (pinfunction "A_1") (pintype "passive"))
    )
    (net (code "36") (name "/ALU_OR2") (class "Default")
      (node (ref "DS7") (pin "1") (pinfunction "A_1") (pintype "passive"))
    )
    (net (code "37") (name "/ALU_OR3") (class "Default")
      (node (ref "DS8") (pin "1") (pinfunction "A_1") (pintype "passive"))
    )
    (net (code "38") (name "/ALU_OUT0") (class "Default")
      (node (ref "DS27") (pin "1") (pinfunction "A_1") (pintype "passive"))
      (node (ref "J2") (pin "12") (pinfunction "12_12") (pintype "passive"))
    )
    (net (code "39") (name "/ALU_OUT1") (class "Default")
      (node (ref "DS28") (pin "1") (pinfunction "A_1") (pintype "passive"))
      (node (ref "J2") (pin "10") (pinfunction "10_10") (pintype "passive"))
    )
    (net (code "40") (name "/ALU_OUT2") (class "Default")
      (node (ref "DS29") (pin "1") (pinfunction "A_1") (pintype "passive"))
      (node (ref "J2") (pin "8") (pinfunction "8_8") (pintype "passive"))
    )
    (net (code "41") (name "/ALU_OUT3") (class "Default")
      (node (ref "DS30") (pin "1") (pinfunction "A_1") (pintype "passive"))
      (node (ref "J2") (pin "6") (pinfunction "6_6") (pintype "passive"))
    )
    (net (code "46") (name "/ALU_XOR0") (class "Default")
      (node (ref "DS13") (pin "1") (pinfunction "A_1") (pintype "passive"))
    )
    (net (code "47") (name "/ALU_XOR1") (class "Default")
      (node (ref "DS14") (pin "1") (pinfunction "A_1") (pintype "passive"))
    )
    (net (code "48") (name "/ALU_XOR2") (class "Default")
      (node (ref "DS15") (pin "1") (pinfunction "A_1") (pintype "passive"))
    )
    (net (code "49") (name "/ALU_XOR3") (class "Default")
      (node (ref "DS16") (pin "1") (pinfunction "A_1") (pintype "passive"))
    )
    (net (code "57") (name "/OP_P0") (class "Default")
      (node (ref "DS21") (pin "1") (pinfunction "A_1") (pintype "passive"))
      (node (ref "J1") (pin "5") (pinfunction "5_5") (pintype "passive"))
    )
    (net (code "58") (name "/OP_P1") (class "Default")
      (node (ref "DS22") (pin "1") (pinfunction "A_1") (pintype "passive"))
      (node (ref "J1") (pin "7") (pinfunction "7_7") (pintype "passive"))
    )
    (net (code "59") (name "/OP_P2") (class "Default")
      (node (ref "DS23") (pin "1") (pinfunction "A_1") (pintype "passive"))
      (node (ref "J1") (pin "9") (pinfunction "9_9") (pintype "passive"))
    )
    (net (code "60") (name "/OP_P3") (class "Default")
      (node (ref "DS24") (pin "1") (pinfunction "A_1") (pintype "passive"))
      (node (ref "J1") (pin "11") (pinfunction "11_11") (pintype "passive"))
    )
    (net (code "81") (name "GND") (class "Default")
      (node (ref "J1") (pin "17") (pinfunction "17_17") (pintype "passive"))
      (node (ref "J1") (pin "18") (pinfunction "18_18") (pintype "passive"))
      (node (ref "J1") (pin "19") (pinfunction "19_19") (pintype "passive"))
      (node (ref "J1") (pin "20") (pinfunction "20_20") (pintype "passive"))
      (node (ref "J2") (pin "17") (pinfunction "17_17") (pintype "passive"))
      (node (ref "J2") (pin "18") (pinfunction "18_18") (pintype "passive"))
      (node (ref "J2") (pin "19") (pinfunction "19_19") (pintype "passive"))
      (node (ref "J2") (pin "20") (pinfunction "20_20") (pintype "passive"))
      (node (ref "R1") (pin "2") (pinfunction "2_2") (pintype "passive"))
      (node (ref "R10") (pin "2") (pinfunction "2_2") (pintype "passive"))
      (node (ref "R11") (pin "2") (pinfunction "2_2") (pintype "passive"))
      (node (ref "R12") (pin "2") (pinfunction "2_2") (pintype "passive"))
      (node (ref "R13") (pin "2") (pinfunction "2_2") (pintype "passive"))
      (node (ref "R14") (pin "2") (pinfunction "2_2") (pintype "passive"))
      (node (ref "R15") (pin "2") (pinfunction "2_2") (pintype "passive"))
      (node (ref "R16") (pin "2") (pinfunction "2_2") (pintype "passive"))
      (node (ref "R17") (pin "2") (pinfunction "2_2") (pintype "passive"))
      (node (ref "R18") (pin "2") (pinfunction "2_2") (pintype "passive"))
      (node (ref "R19") (pin "2") (pinfunction "2_2") (pintype "passive"))
      (node (ref "R2") (pin "2") (pinfunction "2_2") (pintype "passive"))
      (node (ref "R20") (pin "2") (pinfunction "2_2") (pintype "passive"))
      (node (ref "R21") (pin "2") (pinfunction "2_2") (pintype "passive"))
      (node (ref "R22") (pin "2") (pinfunction "2_2") (pintype "passive"))
      (node (ref "R23") (pin "2") (pinfunction "2_2") (pintype "passive"))
      (node (ref "R24") (pin "2") (pinfunction "2_2") (pintype "passive"))
      (node (ref "R25") (pin "2") (pinfunction "2_2") (pintype "passive"))
      (node (ref "R26") (pin "2") (pinfunction "2_2") (pintype "passive"))
      (node (ref "R27") (pin "2") (pinfunction "2_2") (pintype "passive"))
      (node (ref "R28") (pin "2") (pinfunction "2_2") (pintype "passive"))
      (node (ref "R29") (pin "2") (pinfunction "2_2") (pintype "passive"))
      (node (ref "R3") (pin "2") (pinfunction "2_2") (pintype "passive"))
      (node (ref "R30") (pin "2") (pinfunction "2_2") (pintype "passive"))
      (node (ref "R31") (pin "2") (pinfunction "2_2") (pintype "passive"))
      (node (ref "R32") (pin "2") (pinfunction "2_2") (pintype "passive"))
      (node (ref "R33") (pin "2") (pinfunction "2_2") (pintype "passive"))
      (node (ref "R34") (pin "2") (pinfunction "2_2") (pintype "passive"))
      (node (ref "R35") (pin "2") (pinfunction "2_2") (pintype "passive"))
      (node (ref "R36") (pin "2") (pinfunction "2_2") (pintype "passive"))
      (node (ref "R37") (pin "2") (pinfunction "2_2") (pintype "passive"))
      (node (ref "R38") (pin "2") (pinfunction "2_2") (pintype "passive"))
      (node (ref "R39") (pin "2") (pinfunction "2_2") (pintype "passive"))
      (node (ref "R4") (pin "2") (pinfunction "2_2") (pintype "passive"))
      (node (ref "R40") (pin "2") (pinfunction "2_2") (pintype "passive"))
      (node (ref "R41") (pin "2") (pinfunction "2_2") (pintype "passive"))
      (node (ref "R42") (pin "2") (pinfunction "2_2") (pintype "passive"))
      (node (ref "R5") (pin "2") (pinfunction "2_2") (pintype "passive"))
      (node (ref "R6") (pin "2") (pinfunction "2_2") (pintype "passive"))
      (node (ref "R7") (pin "2") (pinfunction "2_2") (pintype "passive"))
      (node (ref "R8") (pin "2") (pinfunction "2_2") (pintype "passive"))
      (node (ref "R9") (pin "2") (pinfunction "2_2") (pintype "passive"))
    )
    (net (code "82") (name "Net-(DS1-K)") (class "Default")
      (node (ref "DS1") (pin "2") (pinfunction "K_2") (pintype "passive"))
      (node (ref "R1") (pin "1") (pinfunction "1_1") (pintype "passive"))
    )
    (net (code "83") (name "Net-(DS2-K)") (class "Default")
      (node (ref "DS2") (pin "2") (pinfunction "K_2") (pintype "passive"))
      (node (ref "R2") (pin "1") (pinfunction "1_1") (pintype "passive"))
    )
    (net (code "84") (name "Net-(DS3-K)") (class "Default")
      (node (ref "DS3") (pin "2") (pinfunction "K_2") (pintype "passive"))
      (node (ref "R3") (pin "1") (pinfunction "1_1") (pintype "passive"))
    )
    (net (code "85") (name "Net-(DS4-K)") (class "Default")
      (node (ref "DS4") (pin "2") (pinfunction "K_2") (pintype "passive"))
      (node (ref "R4") (pin "1") (pinfunction "1_1") (pintype "passive"))
    )
    (net (code "86") (name "Net-(DS5-K)") (class "Default")
      (node (ref "DS5") (pin "2") (pinfunction "K_2") (pintype "passive"))
      (node (ref "R5") (pin "1") (pinfunction "1_1") (pintype "passive"))
    )
    (net (code "87") (name "Net-(DS6-K)") (class "Default")
      (node (ref "DS6") (pin "2") (pinfunction "K_2") (pintype "passive"))
      (node (ref "R6") (pin "1") (pinfunction "1_1") (pintype "passive"))
    )
    (net (code "88") (name "Net-(DS7-K)") (class "Default")
      (node (ref "DS7") (pin "2") (pinfunction "K_2") (pintype "passive"))
      (node (ref "R7") (pin "1") (pinfunction "1_1") (pintype "passive"))
    )
    (net (code "89") (name "Net-(DS8-K)") (class "Default")
      (node (ref "DS8") (pin "2") (pinfunction "K_2") (pintype "passive"))
      (node (ref "R8") (pin "1") (pinfunction "1_1") (pintype "passive"))
    )
    (net (code "90") (name "Net-(DS9-K)") (class "Default")
      (node (ref "DS9") (pin "2") (pinfunction "K_2") (pintype "passive"))
      (node (ref "R9") (pin "1") (pinfunction "1_1") (pintype "passive"))
    )
    (net (code "91") (name "Net-(DS10-K)") (class "Default")
      (node (ref "DS10") (pin "2") (pinfunction "K_2") (pintype "passive"))
      (node (ref "R10") (pin "1") (pinfunction "1_1") (pintype "passive"))
    )
    (net (code "92") (name "Net-(DS11-K)") (class "Default")
      (node (ref "DS11") (pin "2") (pinfunction "K_2") (pintype "passive"))
      (node (ref "R11") (pin "1") (pinfunction "1_1") (pintype "passive"))
    )
    (net (code "93") (name "Net-(DS12-K)") (class "Default")
      (node (ref "DS12") (pin "2") (pinfunction "K_2") (pintype "passive"))
      (node (ref "R12") (pin "1") (pinfunction "1_1") (pintype "passive"))
    )
    (net (code "94") (name "Net-(DS13-K)") (class "Default")
      (node (ref "DS13") (pin "2") (pinfunction "K_2") (pintype "passive"))
      (node (ref "R13") (pin "1") (pinfunction "1_1") (pintype "passive"))
    )
    (net (code "95") (name "Net-(DS14-K)") (class "Default")
      (node (ref "DS14") (pin "2") (pinfunction "K_2") (pintype "passive"))
      (node (ref "R14") (pin "1") (pinfunction "1_1") (pintype "passive"))
    )
    (net (code "96") (name "Net-(DS15-K)") (class "Default")
      (node (ref "DS15") (pin "2") (pinfunction "K_2") (pintype "passive"))
      (node (ref "R15") (pin "1") (pinfunction "1_1") (pintype "passive"))
    )
    (net (code "97") (name "Net-(DS16-K)") (class "Default")
      (node (ref "DS16") (pin "2") (pinfunction "K_2") (pintype "passive"))
      (node (ref "R16") (pin "1") (pinfunction "1_1") (pintype "passive"))
    )
    (net (code "98") (name "Net-(DS17-K)") (class "Default")
      (node (ref "DS17") (pin "2") (pinfunction "K_2") (pintype "passive"))
      (node (ref "R17") (pin "1") (pinfunction "1_1") (pintype "passive"))
    )
    (net (code "99") (name "Net-(DS18-K)") (class "Default")
      (node (ref "DS18") (pin "2") (pinfunction "K_2") (pintype "passive"))
      (node (ref "R18") (pin "1") (pinfunction "1_1") (pintype "passive"))
    )
    (net (code "100") (name "Net-(DS19-K)") (class "Default")
      (node (ref "DS19") (pin "2") (pinfunction "K_2") (pintype "passive"))
      (node (ref "R19") (pin "1") (pinfunction "1_1") (pintype "passive"))
    )
    (net (code "101") (name "Net-(DS20-K)") (class "Default")
      (node (ref "DS20") (pin "2") (pinfunction "K_2") (pintype "passive"))
      (node (ref "R20") (pin "1") (pinfunction "1_1") (pintype "passive"))
    )
    (net (code "102") (name "Net-(DS21-K)") (class "Default")
      (node (ref "DS21") (pin "2") (pinfunction "K_2") (pintype "passive"))
      (node (ref "R21") (pin "1") (pinfunction "1_1") (pintype "passive"))
    )
    (net (code "103") (name "Net-(DS22-K)") (class "Default")
      (node (ref "DS22") (pin "2") (pinfunction "K_2") (pintype "passive"))
      (node (ref "R22") (pin "1") (pinfunction "1_1") (pintype "passive"))
    )
    (net (code "104") (name "Net-(DS23-K)") (class "Default")
      (node (ref "DS23") (pin "2") (pinfunction "K_2") (pintype "passive"))
      (node (ref "R23") (pin "1") (pinfunction "1_1") (pintype "passive"))
    )
    (net (code "105") (name "Net-(DS24-K)") (class "Default")
      (node (ref "DS24") (pin "2") (pinfunction "K_2") (pintype "passive"))
      (node (ref "R24") (pin "1") (pinfunction "1_1") (pintype "passive"))
    )
    (net (code "106") (name "Net-(DS25-K)") (class "Default")
      (node (ref "DS25") (pin "2") (pinfunction "K_2") (pintype "passive"))
      (node (ref "R25") (pin "1") (pinfunction "1_1") (pintype "passive"))
    )
    (net (code "107") (name "Net-(DS26-K)") (class "Default")
      (node (ref "DS26") (pin "2") (pinfunction "K_2") (pintype "passive"))
      (node (ref "R26") (pin "1") (pinfunction "1_1") (pintype "passive"))
    )
    (net (code "108") (name "Net-(DS27-K)") (class "Default")
      (node (ref "DS27") (pin "2") (pinfunction "K_2") (pintype "passive"))
      (node (ref "R27") (pin "1") (pinfunction "1_1") (pintype "passive"))
    )
    (net (code "109") (name "Net-(DS28-K)") (class "Default")
      (node (ref "DS28") (pin "2") (pinfunction "K_2") (pintype "passive"))
      (node (ref "R28") (pin "1") (pinfunction "1_1") (pintype "passive"))
    )
    (net (code "110") (name "Net-(DS29-K)") (class "Default")
      (node (ref "DS29") (pin "2") (pinfunction "K_2") (pintype "passive"))
      (node (ref "R29") (pin "1") (pinfunction "1_1") (pintype "passive"))
    )
    (net (code "111") (name "Net-(DS30-K)") (class "Default")
      (node (ref "DS30") (pin "2") (pinfunction "K_2") (pintype "passive"))
      (node (ref "R30") (pin "1") (pinfunction "1_1") (pintype "passive"))
    )
    (net (code "112") (name "Net-(DS31-K)") (class "Default")
      (node (ref "DS31") (pin "2") (pinfunction "K_2") (pintype "passive"))
      (node (ref "R31") (pin "1") (pinfunction "1_1") (pintype "passive"))
    )
    (net (code "113") (name "Net-(DS32-K)") (class "Default")
      (node (ref "DS32") (pin "2") (pinfunction "K_2") (pintype "passive"))
      (node (ref "R32") (pin "1") (pinfunction "1_1") (pintype "passive"))
    )
    (net (code "114") (name "Net-(DS33-K)") (class "Default")
      (node (ref "DS33") (pin "2") (pinfunction "K_2") (pintype "passive"))
      (node (ref "R33") (pin "1") (pinfunction "1_1") (pintype "passive"))
    )
    (net (code "115") (name "Net-(DS34-K)") (class "Default")
      (node (ref "DS34") (pin "2") (pinfunction "K_2") (pintype "passive"))
      (node (ref "R34") (pin "1") (pinfunction "1_1") (pintype "passive"))
    )
    (net (code "116") (name "Net-(DS35-K)") (class "Default")
      (node (ref "DS35") (pin "2") (pinfunction "K_2") (pintype "passive"))
      (node (ref "R35") (pin "1") (pinfunction "1_1") (pintype "passive"))
    )
    (net (code "117") (name "Net-(DS36-K)") (class "Default")
      (node (ref "DS36") (pin "2") (pinfunction "K_2") (pintype "passive"))
      (node (ref "R36") (pin "1") (pinfunction "1_1") (pintype "passive"))
    )
    (net (code "118") (name "Net-(DS37-K)") (class "Default")
      (node (ref "DS37") (pin "2") (pinfunction "K_2") (pintype "passive"))
      (node (ref "R37") (pin "1") (pinfunction "1_1") (pintype "passive"))
    )
    (net (code "119") (name "Net-(DS38-K)") (class "Default")
      (node (ref "DS38") (pin "2") (pinfunction "K_2") (pintype "passive"))
      (node (ref "R38") (pin "1") (pinfunction "1_1") (pintype "passive"))
    )
    (net (code "120") (name "Net-(DS39-K)") (class "Default")
      (node (ref "DS39") (pin "2") (pinfunction "K_2") (pintype "passive"))
      (node (ref "R39") (pin "1") (pinfunction "1_1") (pintype "passive"))
    )
    (net (code "121") (name "Net-(DS40-K)") (class "Default")
      (node (ref "DS40") (pin "2") (pinfunction "K_2") (pintype "passive"))
      (node (ref "R40") (pin "1") (pinfunction "1_1") (pintype "passive"))
    )
    (net (code "122") (name "Net-(DS41-K)") (class "Default")
      (node (ref "DS41") (pin "2") (pinfunction "K_2") (pintype "passive"))
      (node (ref "R41") (pin "1") (pinfunction "1_1") (pintype "passive"))
    )
    (net (code "123") (name "Net-(DS42-K)") (class "Default")
      (node (ref "DS42") (pin "2") (pinfunction "K_2") (pintype "passive"))
      (node (ref "R42") (pin "1") (pinfunction "1_1") (pintype "passive"))
    )
    (net (code "124") (name "unconnected-(J2-Pad5)") (class "Default")
      (node (ref "J2") (pin "5") (pinfunction "5_5") (pintype "passive"))
    )
    (net (code "125") (name "unconnected-(J2-Pad7)") (class "Default")
      (node (ref "J2") (pin "7") (pinfunction "7_7") (pintype "passive"))
    )
    (net (code "126") (name "unconnected-(J2-Pad9)") (class "Default")
      (node (ref "J2") (pin "9") (pinfunction "9_9") (pintype "passive"))
    )
    (net (code "127") (name "unconnected-(J2-Pad11)") (class "Default")
      (node (ref "J2") (pin "11") (pinfunction "11_11") (pintype "passive"))
    )
    (net (code "128") (name "unconnected-(J2-Pad13)") (class "Default")
      (node (ref "J2") (pin "13") (pinfunction "13_13") (pintype "passive"))
    )
    (net (code "129") (name "unconnected-(J2-Pad15)") (class "Default")
      (node (ref "J2") (pin "15") (pinfunction "15_15") (pintype "passive"))
    )
  )
)
